# Sheet1.net
KiCad netlist of a schematic drawn in Altium Designer
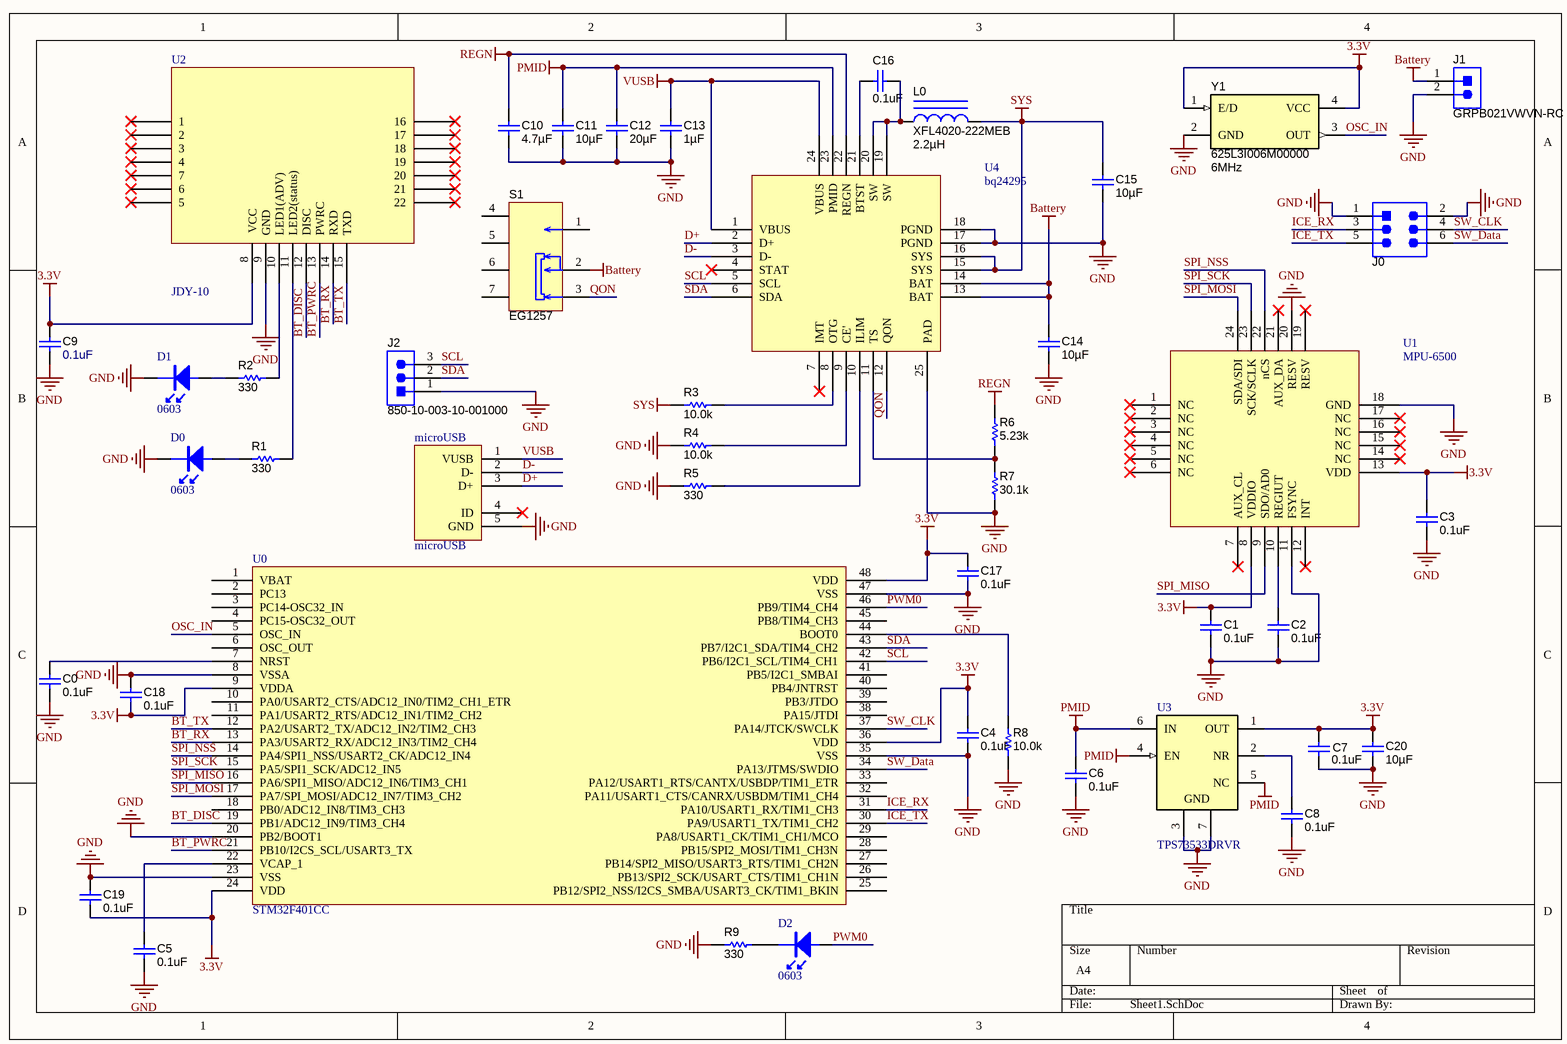
[diagram p0: Sheet1.SchDoc]

(export (version "E")
  (design (tool "Eeschema 10.0.6"))
  (components
    (comp (ref "C0")
      (value "0402YC132KAT2A")
      (footprint "0402S")
      (description "CAP, CERM, 1300 pF, 16 V, +/- 10%, X7R, 0402")
      (fields
        (field (name "VALUEDISPLAYED") "0.1uF")
        (field (name "MANUFACTURER") "AVX")
        (field (name "PUBLISHER") "Texas Instruments")
      )
      (libsource (lib "Capacitor_Ceramic") (part "0402YC132KAT2A"))
    )
    (comp (ref "C1")
      (value "0402YC132KAT2A")
      (footprint "0402S")
      (description "CAP, CERM, 1300 pF, 16 V, +/- 10%, X7R, 0402")
      (fields
        (field (name "VALUEDISPLAYED") "0.1uF")
        (field (name "MANUFACTURER") "AVX")
        (field (name "PUBLISHER") "Texas Instruments")
      )
      (libsource (lib "Capacitor_Ceramic") (part "0402YC132KAT2A"))
    )
    (comp (ref "C2")
      (value "0402YC132KAT2A")
      (footprint "0402S")
      (description "CAP, CERM, 1300 pF, 16 V, +/- 10%, X7R, 0402")
      (fields
        (field (name "VALUEDISPLAYED") "0.1uF")
        (field (name "MANUFACTURER") "AVX")
        (field (name "PUBLISHER") "Texas Instruments")
      )
      (libsource (lib "Capacitor_Ceramic") (part "0402YC132KAT2A"))
    )
    (comp (ref "C3")
      (value "0402YC132KAT2A")
      (footprint "0402S")
      (description "CAP, CERM, 1300 pF, 16 V, +/- 10%, X7R, 0402")
      (fields
        (field (name "VALUEDISPLAYED") "0.1uF")
        (field (name "MANUFACTURER") "AVX")
        (field (name "PUBLISHER") "Texas Instruments")
      )
      (libsource (lib "Capacitor_Ceramic") (part "0402YC132KAT2A"))
    )
    (comp (ref "C4")
      (value "0402YC132KAT2A")
      (footprint "0402S")
      (description "CAP, CERM, 1300 pF, 16 V, +/- 10%, X7R, 0402")
      (fields
        (field (name "VALUEDISPLAYED") "0.1uF")
        (field (name "MANUFACTURER") "AVX")
        (field (name "PUBLISHER") "Texas Instruments")
      )
      (libsource (lib "Capacitor_Ceramic") (part "0402YC132KAT2A"))
    )
    (comp (ref "C5")
      (value "0402YC132KAT2A")
      (footprint "0402S")
      (description "CAP, CERM, 1300 pF, 16 V, +/- 10%, X7R, 0402")
      (fields
        (field (name "VALUEDISPLAYED") "0.1uF")
        (field (name "MANUFACTURER") "AVX")
        (field (name "PUBLISHER") "Texas Instruments")
      )
      (libsource (lib "Capacitor_Ceramic") (part "0402YC132KAT2A"))
    )
    (comp (ref "C6")
      (value "0402YC132KAT2A")
      (footprint "0402S")
      (description "CAP, CERM, 1300 pF, 16 V, +/- 10%, X7R, 0402")
      (fields
        (field (name "VALUEDISPLAYED") "0.1uF")
        (field (name "MANUFACTURER") "AVX")
        (field (name "PUBLISHER") "Texas Instruments")
      )
      (libsource (lib "Capacitor_Ceramic") (part "0402YC132KAT2A"))
    )
    (comp (ref "C7")
      (value "0402YC132KAT2A")
      (footprint "0402S")
      (description "CAP, CERM, 1300 pF, 16 V, +/- 10%, X7R, 0402")
      (fields
        (field (name "VALUEDISPLAYED") "0.1uF")
        (field (name "MANUFACTURER") "AVX")
        (field (name "PUBLISHER") "Texas Instruments")
      )
      (libsource (lib "Capacitor_Ceramic") (part "0402YC132KAT2A"))
    )
    (comp (ref "C8")
      (value "0402YC132KAT2A")
      (footprint "0402S")
      (description "CAP, CERM, 1300 pF, 16 V, +/- 10%, X7R, 0402")
      (fields
        (field (name "VALUEDISPLAYED") "0.1uF")
        (field (name "MANUFACTURER") "AVX")
        (field (name "PUBLISHER") "Texas Instruments")
      )
      (libsource (lib "Capacitor_Ceramic") (part "0402YC132KAT2A"))
    )
    (comp (ref "C9")
      (value "0402YC132KAT2A")
      (footprint "0402S")
      (description "CAP, CERM, 1300 pF, 16 V, +/- 10%, X7R, 0402")
      (fields
        (field (name "VALUEDISPLAYED") "0.1uF")
        (field (name "MANUFACTURER") "AVX")
        (field (name "PUBLISHER") "Texas Instruments")
      )
      (libsource (lib "Capacitor_Ceramic") (part "0402YC132KAT2A"))
    )
    (comp (ref "C10")
      (value "VJ1206Y473KXEAT5Z")
      (footprint "0603L")
      (description "CAP, CERM, 0.047 µF, 500 V, +/- 10%, X7R, 1206")
      (fields
        (field (name "VALUEDISPLAYED") "4.7µF")
        (field (name "MANUFACTURER") "Vishay-Vitramon")
        (field (name "PUBLISHER") "Texas Instruments")
      )
      (libsource (lib "Capacitor_Ceramic") (part "VJ1206Y473KXEAT5Z"))
    )
    (comp (ref "C11")
      (value "VJ1206Y473KXEAT5Z")
      (footprint "0805L")
      (description "CAP, CERM, 0.047 µF, 500 V, +/- 10%, X7R, 1206")
      (fields
        (field (name "VALUEDISPLAYED") "10µF")
        (field (name "MANUFACTURER") "Vishay-Vitramon")
        (field (name "PUBLISHER") "Texas Instruments")
      )
      (libsource (lib "Capacitor_Ceramic") (part "VJ1206Y473KXEAT5Z"))
    )
    (comp (ref "C12")
      (value "VJ1206Y473KXEAT5Z")
      (footprint "0805L")
      (description "CAP, CERM, 0.047 µF, 500 V, +/- 10%, X7R, 1206")
      (fields
        (field (name "VALUEDISPLAYED") "20µF")
        (field (name "MANUFACTURER") "Vishay-Vitramon")
        (field (name "PUBLISHER") "Texas Instruments")
      )
      (libsource (lib "Capacitor_Ceramic") (part "VJ1206Y473KXEAT5Z"))
    )
    (comp (ref "C13")
      (value "0402YC132KAT2A")
      (footprint "0402S")
      (description "CAP, CERM, 1300 pF, 16 V, +/- 10%, X7R, 0402")
      (fields
        (field (name "VALUEDISPLAYED") "1µF")
        (field (name "MANUFACTURER") "AVX")
        (field (name "PUBLISHER") "Texas Instruments")
      )
      (libsource (lib "Capacitor_Ceramic") (part "0402YC132KAT2A"))
    )
    (comp (ref "C14")
      (value "VJ1206Y473KXEAT5Z")
      (footprint "0805L")
      (description "CAP, CERM, 0.047 µF, 500 V, +/- 10%, X7R, 1206")
      (fields
        (field (name "VALUEDISPLAYED") "10µF")
        (field (name "MANUFACTURER") "Vishay-Vitramon")
        (field (name "PUBLISHER") "Texas Instruments")
      )
      (libsource (lib "Capacitor_Ceramic") (part "VJ1206Y473KXEAT5Z"))
    )
    (comp (ref "C15")
      (value "VJ1206Y473KXEAT5Z")
      (footprint "0805L")
      (description "CAP, CERM, 0.047 µF, 500 V, +/- 10%, X7R, 1206")
      (fields
        (field (name "VALUEDISPLAYED") "10µF")
        (field (name "MANUFACTURER") "Vishay-Vitramon")
        (field (name "PUBLISHER") "Texas Instruments")
      )
      (libsource (lib "Capacitor_Ceramic") (part "VJ1206Y473KXEAT5Z"))
    )
    (comp (ref "C16")
      (value "0402YC132KAT2A")
      (footprint "0402S")
      (description "CAP, CERM, 1300 pF, 16 V, +/- 10%, X7R, 0402")
      (fields
        (field (name "VALUEDISPLAYED") "0.1uF")
        (field (name "MANUFACTURER") "AVX")
        (field (name "PUBLISHER") "Texas Instruments")
      )
      (libsource (lib "Capacitor_Ceramic") (part "0402YC132KAT2A"))
    )
    (comp (ref "C17")
      (value "0402YC132KAT2A")
      (footprint "0402S")
      (description "CAP, CERM, 1300 pF, 16 V, +/- 10%, X7R, 0402")
      (fields
        (field (name "VALUEDISPLAYED") "0.1uF")
        (field (name "MANUFACTURER") "AVX")
        (field (name "PUBLISHER") "Texas Instruments")
      )
      (libsource (lib "Capacitor_Ceramic") (part "0402YC132KAT2A"))
    )
    (comp (ref "C18")
      (value "0402YC132KAT2A")
      (footprint "0402S")
      (description "CAP, CERM, 1300 pF, 16 V, +/- 10%, X7R, 0402")
      (fields
        (field (name "VALUEDISPLAYED") "0.1uF")
        (field (name "MANUFACTURER") "AVX")
        (field (name "PUBLISHER") "Texas Instruments")
      )
      (libsource (lib "Capacitor_Ceramic") (part "0402YC132KAT2A"))
    )
    (comp (ref "C19")
      (value "0402YC132KAT2A")
      (footprint "0402S")
      (description "CAP, CERM, 1300 pF, 16 V, +/- 10%, X7R, 0402")
      (fields
        (field (name "VALUEDISPLAYED") "0.1uF")
        (field (name "MANUFACTURER") "AVX")
        (field (name "PUBLISHER") "Texas Instruments")
      )
      (libsource (lib "Capacitor_Ceramic") (part "0402YC132KAT2A"))
    )
    (comp (ref "C20")
      (value "VJ1206Y473KXEAT5Z")
      (footprint "0805L")
      (description "CAP, CERM, 0.047 µF, 500 V, +/- 10%, X7R, 1206")
      (fields
        (field (name "VALUEDISPLAYED") "10µF")
        (field (name "MANUFACTURER") "Vishay-Vitramon")
        (field (name "PUBLISHER") "Texas Instruments")
      )
      (libsource (lib "Capacitor_Ceramic") (part "VJ1206Y473KXEAT5Z"))
    )
    (comp (ref "D0")
      (value "0603")
      (footprint "LED_0603")
      (libsource (lib "Basic_part_ecsl") (part "LED_0603"))
    )
    (comp (ref "D1")
      (value "0603")
      (footprint "LED_0603")
      (libsource (lib "Basic_part_ecsl") (part "LED_0603"))
    )
    (comp (ref "D2")
      (value "0603")
      (footprint "LED_0603")
      (libsource (lib "Basic_part_ecsl") (part "LED_0603"))
    )
    (comp (ref "J0")
      (value "GRPB032VWVN-RC")
      (footprint "Sullins_GRPB032VWVN-RC")
      (description "Header, 50mil, 3x2, Gold, TH")
      (fields
        (field (name "MANUFACTURER") "Sullins Connector Solutions")
        (field (name "SYMBOLCREATOR") "a0412235")
        (field (name "PUBLISHER") "Texas Instruments")
      )
      (libsource (lib "Connectors") (part "GRPB032VWVN-RC"))
    )
    (comp (ref "J1")
      (value "GRPB021VWVN-RC")
      (footprint "Sullins_GRPB021VWVN-RC")
      (description "Header, 50mil, 2x1, Gold, TH")
      (fields
        (field (name "MANUFACTURER") "Sullins Connector Solutions")
        (field (name "SYMBOLCREATOR") "a0412235")
        (field (name "PUBLISHER") "Texas Instruments")
      )
      (libsource (lib "Connectors") (part "GRPB021VWVN-RC"))
    )
    (comp (ref "J2")
      (value "850-10-003-10-001000")
      (footprint "Mill-Max_850-10-003-10-001000")
      (description "Header, 50mil, 3x1, Gold, TH")
      (fields
        (field (name "MANUFACTURER") "Mill-Max")
        (field (name "SYMBOLCREATOR") "a0799628")
        (field (name "PUBLISHER") "Texas Instruments")
      )
      (libsource (lib "Connectors") (part "850-10-003-10-001000"))
    )
    (comp (ref "L0")
      (value "XFL4020-222MEB")
      (footprint "XFL4020")
      (description "Inductor, Shielded, Composite, 2.2uH, 3.7A, 0.02 ohm, SMD")
      (fields
        (field (name "VALUEDISPLAYED") "2.2µH")
        (field (name "MANUFACTURER") "Coilcraft")
        (field (name "PUBLISHER") "Texas Instruments")
      )
      (libsource (lib "Inductor") (part "XFL4020-222MEB"))
    )
    (comp (ref "microUSB")
      (value "microUSB")
      (footprint "Micro_USB")
      (libsource (lib "Basic_part_ecsl") (part "microUSB"))
    )
    (comp (ref "R1")
      (value "PCF0402-12-10KBT1")
      (footprint "0402S")
      (description "RES, 10.0 k, 0.1%, 0.063 W, 0402")
      (fields
        (field (name "VALUEDISPLAYED") "330")
        (field (name "MANUFACTURER") "TT Electronics/IRC")
        (field (name "PUBLISHER") "Texas Instruments")
      )
      (libsource (lib "Resistor_0402") (part "PCF0402-12-10KBT1"))
    )
    (comp (ref "R2")
      (value "PCF0402-12-10KBT1")
      (footprint "0402S")
      (description "RES, 10.0 k, 0.1%, 0.063 W, 0402")
      (fields
        (field (name "VALUEDISPLAYED") "330")
        (field (name "MANUFACTURER") "TT Electronics/IRC")
        (field (name "PUBLISHER") "Texas Instruments")
      )
      (libsource (lib "Resistor_0402") (part "PCF0402-12-10KBT1"))
    )
    (comp (ref "R3")
      (value "PCF0402-12-10KBT1")
      (footprint "0402S")
      (description "RES, 10.0 k, 0.1%, 0.063 W, 0402")
      (fields
        (field (name "VALUEDISPLAYED") "10.0k")
        (field (name "MANUFACTURER") "TT Electronics/IRC")
        (field (name "PUBLISHER") "Texas Instruments")
      )
      (libsource (lib "Resistor_0402") (part "PCF0402-12-10KBT1"))
    )
    (comp (ref "R4")
      (value "PCF0402-12-10KBT1")
      (footprint "0402S")
      (description "RES, 10.0 k, 0.1%, 0.063 W, 0402")
      (fields
        (field (name "VALUEDISPLAYED") "10.0k")
        (field (name "MANUFACTURER") "TT Electronics/IRC")
        (field (name "PUBLISHER") "Texas Instruments")
      )
      (libsource (lib "Resistor_0402") (part "PCF0402-12-10KBT1"))
    )
    (comp (ref "R5")
      (value "PCF0402-12-10KBT1")
      (footprint "0402S")
      (description "RES, 10.0 k, 0.1%, 0.063 W, 0402")
      (fields
        (field (name "VALUEDISPLAYED") "330")
        (field (name "MANUFACTURER") "TT Electronics/IRC")
        (field (name "PUBLISHER") "Texas Instruments")
      )
      (libsource (lib "Resistor_0402") (part "PCF0402-12-10KBT1"))
    )
    (comp (ref "R6")
      (value "PCF0402-12-10KBT1")
      (footprint "0402S")
      (description "RES, 10.0 k, 0.1%, 0.063 W, 0402")
      (fields
        (field (name "VALUEDISPLAYED") "5.23k")
        (field (name "MANUFACTURER") "TT Electronics/IRC")
        (field (name "PUBLISHER") "Texas Instruments")
      )
      (libsource (lib "Resistor_0402") (part "PCF0402-12-10KBT1"))
    )
    (comp (ref "R7")
      (value "PCF0402-12-10KBT1")
      (footprint "0402S")
      (description "RES, 10.0 k, 0.1%, 0.063 W, 0402")
      (fields
        (field (name "VALUEDISPLAYED") "30.1k")
        (field (name "MANUFACTURER") "TT Electronics/IRC")
        (field (name "PUBLISHER") "Texas Instruments")
      )
      (libsource (lib "Resistor_0402") (part "PCF0402-12-10KBT1"))
    )
    (comp (ref "R8")
      (value "PCF0402-12-10KBT1")
      (footprint "0402S")
      (description "RES, 10.0 k, 0.1%, 0.063 W, 0402")
      (fields
        (field (name "VALUEDISPLAYED") "10.0k")
        (field (name "MANUFACTURER") "TT Electronics/IRC")
        (field (name "PUBLISHER") "Texas Instruments")
      )
      (libsource (lib "Resistor_0402") (part "PCF0402-12-10KBT1"))
    )
    (comp (ref "R9")
      (value "PCF0402-12-10KBT1")
      (footprint "0402S")
      (description "RES, 10.0 k, 0.1%, 0.063 W, 0402")
      (fields
        (field (name "VALUEDISPLAYED") "330")
        (field (name "MANUFACTURER") "TT Electronics/IRC")
        (field (name "PUBLISHER") "Texas Instruments")
      )
      (libsource (lib "Resistor_0402") (part "PCF0402-12-10KBT1"))
    )
    (comp (ref "S1")
      (value "EG1257")
      (footprint "SW_EG1257")
      (description "Switch, Slide, SPDT, 0.3A, SMT")
      (fields
        (field (name "MANUFACTURER") "E-Switch")
        (field (name "SYMBOLCREATOR") "a0411947")
        (field (name "PUBLISHER") "Texas Instruments")
      )
      (libsource (lib "Switches") (part "EG1257"))
    )
    (comp (ref "U0")
      (value "STM32F401CC")
      (footprint "RSL0048B_NV")
      (libsource (lib "main") (part "STM32F401CC"))
    )
    (comp (ref "U1")
      (value "MPU-6500")
      (footprint "QFN24 (3x3x0.9)")
      (libsource (lib "Basic_part_ecsl") (part "MPU-6500"))
    )
    (comp (ref "U2")
      (value "JDY-10")
      (footprint "PCBComponent_1")
      (libsource (lib "JDY-10") (part "Component_1"))
    )
    (comp (ref "U3")
      (value "TPS73533DRVR")
      (footprint "DRV0006A")
      (fields
        (field (name "MANUFACTURER") "Texas Instruments")
        (field (name "ALTERNATE PARTNUMBER") "Equivalent")
      )
      (libsource (lib "TI Power Management Linear Regulator Single Channel LDO (400-7500mA)") (part "TPS73533DRVR"))
    )
    (comp (ref "U4")
      (value "bq24295")
      (footprint "RGE0024H_NV")
      (libsource (lib "Basic_part_ecsl") (part "bq24295"))
    )
    (comp (ref "Y1")
      (value "625L3I006M00000")
      (footprint "OSC_CTS_625")
      (description "Oscillator, 6MHz, 3.3V, SMD")
      (fields
        (field (name "FREQUENCY") "6MHz")
        (field (name "MANUFACTURER") "CTS Electrocomponents")
        (field (name "SYMBOLCREATOR") "a0411947")
        (field (name "PUBLISHER") "Texas Instruments")
      )
      (libsource (lib "Oscillators") (part "625L3I006M00000"))
    )
  )
  (nets
    (net (code "1") (name "/BT_DISC") (class "Default")
      (node (ref "U0") (pin "19") (pinfunction "PB1/ADC12_IN9/TIM3_CH4_19") (pintype "passive"))
      (node (ref "U2") (pin "12") (pinfunction "DISC_12") (pintype "passive"))
    )
    (net (code "2") (name "/BT_PWRC") (class "Default")
      (node (ref "U0") (pin "21") (pinfunction "PB10/I2CS_SCL/USART3_TX_21") (pintype "passive"))
      (node (ref "U2") (pin "13") (pinfunction "PWRC_13") (pintype "passive"))
    )
    (net (code "3") (name "/BT_RX") (class "Default")
      (node (ref "U0") (pin "13") (pinfunction "PA3/USART2_RX/ADC12_IN3/TIM2_CH4_13") (pintype "passive"))
      (node (ref "U2") (pin "14") (pinfunction "RXD_14") (pintype "passive"))
    )
    (net (code "4") (name "/BT_TX") (class "Default")
      (node (ref "U0") (pin "12") (pinfunction "PA2/USART2_TX/ADC12_IN2/TIM2_CH3_12") (pintype "passive"))
      (node (ref "U2") (pin "15") (pinfunction "TXD_15") (pintype "passive"))
    )
    (net (code "5") (name "/D+") (class "Default")
      (node (ref "U4") (pin "2") (pinfunction "D+_2") (pintype "passive"))
      (node (ref "microUSB") (pin "3") (pinfunction "D+_3") (pintype "passive"))
    )
    (net (code "6") (name "/D-") (class "Default")
      (node (ref "U4") (pin "3") (pinfunction "D-_3") (pintype "passive"))
      (node (ref "microUSB") (pin "2") (pinfunction "D-_2") (pintype "passive"))
    )
    (net (code "7") (name "/ICE_RX") (class "Default")
      (node (ref "J0") (pin "3") (pinfunction "3_3") (pintype "passive"))
      (node (ref "U0") (pin "31") (pinfunction "PA10/USART1_RX/TIM1_CH3_31") (pintype "passive"))
    )
    (net (code "8") (name "/ICE_TX") (class "Default")
      (node (ref "J0") (pin "5") (pinfunction "5_5") (pintype "passive"))
      (node (ref "U0") (pin "30") (pinfunction "PA9/USART1_TX/TIM1_CH2_30") (pintype "passive"))
    )
    (net (code "9") (name "/OSC_IN") (class "Default")
      (node (ref "U0") (pin "5") (pinfunction "OSC_IN_5") (pintype "passive"))
      (node (ref "Y1") (pin "3") (pinfunction "OUT_3") (pintype "output"))
    )
    (net (code "10") (name "/PWM0") (class "Default")
      (node (ref "D2") (pin "1") (pinfunction "1_1") (pintype "passive"))
      (node (ref "U0") (pin "46") (pinfunction "PB9/TIM4_CH4_46") (pintype "passive"))
    )
    (net (code "11") (name "/QON") (class "Default")
      (node (ref "S1") (pin "3") (pinfunction "3_3") (pintype "passive"))
      (node (ref "U4") (pin "12") (pinfunction "QON_12") (pintype "passive"))
    )
    (net (code "12") (name "/SCL") (class "Default")
      (node (ref "J2") (pin "3") (pinfunction "3_3") (pintype "passive"))
      (node (ref "U0") (pin "42") (pinfunction "PB6/I2C1_SCL/TIM4_CH1_42") (pintype "passive"))
      (node (ref "U4") (pin "5") (pinfunction "SCL_5") (pintype "passive"))
    )
    (net (code "13") (name "/SDA") (class "Default")
      (node (ref "J2") (pin "2") (pinfunction "2_2") (pintype "passive"))
      (node (ref "U0") (pin "43") (pinfunction "PB7/I2C1_SDA/TIM4_CH2_43") (pintype "passive"))
      (node (ref "U4") (pin "6") (pinfunction "SDA_6") (pintype "passive"))
    )
    (net (code "14") (name "/SPI_MISO") (class "Default")
      (node (ref "U0") (pin "16") (pinfunction "PA6/SPI1_MISO/ADC12_IN6/TIM3_CH1_16") (pintype "passive"))
      (node (ref "U1") (pin "9") (pinfunction "SDO/AD0_9") (pintype "passive"))
    )
    (net (code "15") (name "/SPI_MOSI") (class "Default")
      (node (ref "U0") (pin "17") (pinfunction "PA7/SPI_MOSI/ADC12_IN7/TIM3_CH2_17") (pintype "passive"))
      (node (ref "U1") (pin "24") (pinfunction "SDA/SDI_24") (pintype "passive"))
    )
    (net (code "16") (name "/SPI_NSS") (class "Default")
      (node (ref "U0") (pin "14") (pinfunction "PA4/SPI1_NSS/USART2_CK/ADC12_IN4_14") (pintype "passive"))
      (node (ref "U1") (pin "22") (pinfunction "nCS_22") (pintype "passive"))
    )
    (net (code "17") (name "/SPI_SCK") (class "Default")
      (node (ref "U0") (pin "15") (pinfunction "PA5/SPI1_SCK/ADC12_IN5_15") (pintype "passive"))
      (node (ref "U1") (pin "23") (pinfunction "SCK/SCLK_23") (pintype "passive"))
    )
    (net (code "18") (name "/SW_CLK") (class "Default")
      (node (ref "J0") (pin "4") (pinfunction "4_4") (pintype "passive"))
      (node (ref "U0") (pin "37") (pinfunction "PA14/JTCK/SWCLK_37") (pintype "passive"))
    )
    (net (code "19") (name "/SW_Data") (class "Default")
      (node (ref "J0") (pin "6") (pinfunction "6_6") (pintype "passive"))
      (node (ref "U0") (pin "34") (pinfunction "PA13/JTMS/SWDIO_34") (pintype "passive"))
    )
    (net (code "20") (name "3.3V") (class "Default")
      (node (ref "C1") (pin "1") (pinfunction "1_1") (pintype "passive"))
      (node (ref "C17") (pin "1") (pinfunction "1_1") (pintype "passive"))
      (node (ref "C18") (pin "2") (pinfunction "2_2") (pintype "passive"))
      (node (ref "C19") (pin "2") (pinfunction "2_2") (pintype "passive"))
      (node (ref "C20") (pin "1") (pinfunction "1_1") (pintype "passive"))
      (node (ref "C3") (pin "1") (pinfunction "1_1") (pintype "passive"))
      (node (ref "C4") (pin "1") (pinfunction "1_1") (pintype "passive"))
      (node (ref "C7") (pin "1") (pinfunction "1_1") (pintype "passive"))
      (node (ref "C9") (pin "1") (pinfunction "1_1") (pintype "passive"))
      (node (ref "U0") (pin "24") (pinfunction "VDD_24") (pintype "passive"))
      (node (ref "U0") (pin "36") (pinfunction "VDD_36") (pintype "passive"))
      (node (ref "U0") (pin "48") (pinfunction "VDD_48") (pintype "passive"))
      (node (ref "U0") (pin "9") (pinfunction "VDDA_9") (pintype "passive"))
      (node (ref "U1") (pin "13") (pinfunction "VDD_13") (pintype "passive"))
      (node (ref "U1") (pin "8") (pinfunction "VDDIO_8") (pintype "passive"))
      (node (ref "U2") (pin "8") (pinfunction "VCC_8") (pintype "power_in"))
      (node (ref "U3") (pin "1") (pinfunction "OUT_1") (pintype "power_in"))
      (node (ref "Y1") (pin "1") (pinfunction "E/D_1") (pintype "input"))
      (node (ref "Y1") (pin "4") (pinfunction "VCC_4") (pintype "power_in"))
    )
    (net (code "21") (name "Battery") (class "Default")
      (node (ref "C14") (pin "1") (pinfunction "1_1") (pintype "passive"))
      (node (ref "J1") (pin "1") (pinfunction "1_1") (pintype "passive"))
      (node (ref "S1") (pin "2") (pinfunction "2_2") (pintype "passive"))
      (node (ref "U4") (pin "13") (pinfunction "BAT_13") (pintype "passive"))
      (node (ref "U4") (pin "14") (pinfunction "BAT_14") (pintype "passive"))
    )
    (net (code "22") (name "GND") (class "Default")
      (node (ref "C0") (pin "2") (pinfunction "2_2") (pintype "passive"))
      (node (ref "C1") (pin "2") (pinfunction "2_2") (pintype "passive"))
      (node (ref "C10") (pin "2") (pinfunction "2_2") (pintype "passive"))
      (node (ref "C11") (pin "2") (pinfunction "2_2") (pintype "passive"))
      (node (ref "C12") (pin "2") (pinfunction "2_2") (pintype "passive"))
      (node (ref "C13") (pin "2") (pinfunction "2_2") (pintype "passive"))
      (node (ref "C14") (pin "2") (pinfunction "2_2") (pintype "passive"))
      (node (ref "C15") (pin "2") (pinfunction "2_2") (pintype "passive"))
      (node (ref "C17") (pin "2") (pinfunction "2_2") (pintype "passive"))
      (node (ref "C18") (pin "1") (pinfunction "1_1") (pintype "passive"))
      (node (ref "C19") (pin "1") (pinfunction "1_1") (pintype "passive"))
      (node (ref "C2") (pin "2") (pinfunction "2_2") (pintype "passive"))
      (node (ref "C20") (pin "2") (pinfunction "2_2") (pintype "passive"))
      (node (ref "C3") (pin "2") (pinfunction "2_2") (pintype "passive"))
      (node (ref "C4") (pin "2") (pinfunction "2_2") (pintype "passive"))
      (node (ref "C5") (pin "2") (pinfunction "2_2") (pintype "passive"))
      (node (ref "C6") (pin "2") (pinfunction "2_2") (pintype "passive"))
      (node (ref "C7") (pin "2") (pinfunction "2_2") (pintype "passive"))
      (node (ref "C8") (pin "2") (pinfunction "2_2") (pintype "passive"))
      (node (ref "C9") (pin "2") (pinfunction "2_2") (pintype "passive"))
      (node (ref "D0") (pin "2") (pinfunction "2_2") (pintype "passive"))
      (node (ref "D1") (pin "2") (pinfunction "2_2") (pintype "passive"))
      (node (ref "J0") (pin "1") (pinfunction "1_1") (pintype "passive"))
      (node (ref "J0") (pin "2") (pinfunction "2_2") (pintype "passive"))
      (node (ref "J1") (pin "2") (pinfunction "2_2") (pintype "passive"))
      (node (ref "J2") (pin "1") (pinfunction "1_1") (pintype "passive"))
      (node (ref "R4") (pin "1") (pinfunction "1_1") (pintype "passive"))
      (node (ref "R5") (pin "1") (pinfunction "1_1") (pintype "passive"))
      (node (ref "R7") (pin "1") (pinfunction "1_1") (pintype "passive"))
      (node (ref "R8") (pin "1") (pinfunction "1_1") (pintype "passive"))
      (node (ref "R9") (pin "1") (pinfunction "1_1") (pintype "passive"))
      (node (ref "U0") (pin "20") (pinfunction "PB2/BOOT1_20") (pintype "passive"))
      (node (ref "U0") (pin "23") (pinfunction "VSS_23") (pintype "passive"))
      (node (ref "U0") (pin "35") (pinfunction "VSS_35") (pintype "passive"))
      (node (ref "U0") (pin "47") (pinfunction "VSS_47") (pintype "passive"))
      (node (ref "U0") (pin "8") (pinfunction "VSSA_8") (pintype "passive"))
      (node (ref "U1") (pin "11") (pinfunction "FSYNC_11") (pintype "passive"))
      (node (ref "U1") (pin "18") (pinfunction "GND_18") (pintype "passive"))
      (node (ref "U1") (pin "20") (pinfunction "RESV_20") (pintype "passive"))
      (node (ref "U2") (pin "9") (pinfunction "GND_9") (pintype "passive"))
      (node (ref "U3") (pin "3") (pinfunction "GND_3") (pintype "power_in"))
      (node (ref "U3") (pin "7") (pinfunction "GND_7") (pintype "power_in"))
      (node (ref "U4") (pin "17") (pinfunction "PGND_17") (pintype "passive"))
      (node (ref "U4") (pin "18") (pinfunction "PGND_18") (pintype "passive"))
      (node (ref "U4") (pin "25") (pinfunction "PAD_25") (pintype "passive"))
      (node (ref "Y1") (pin "2") (pinfunction "GND_2") (pintype "power_in"))
      (node (ref "microUSB") (pin "5") (pinfunction "GND_5") (pintype "passive"))
    )
    (net (code "23") (name "Net-(C16-Pad1)") (class "Default")
      (node (ref "C16") (pin "1") (pinfunction "1_1") (pintype "passive"))
      (node (ref "L0") (pin "1") (pinfunction "1_1") (pintype "passive"))
      (node (ref "U4") (pin "19") (pinfunction "SW_19") (pintype "passive"))
      (node (ref "U4") (pin "20") (pinfunction "SW_20") (pintype "passive"))
    )
    (net (code "24") (name "Net-(D0-Pad1)") (class "Default")
      (node (ref "D0") (pin "1") (pinfunction "1_1") (pintype "passive"))
      (node (ref "R1") (pin "1") (pinfunction "1_1") (pintype "passive"))
    )
    (net (code "25") (name "Net-(D1-Pad1)") (class "Default")
      (node (ref "D1") (pin "1") (pinfunction "1_1") (pintype "passive"))
      (node (ref "R2") (pin "1") (pinfunction "1_1") (pintype "passive"))
    )
    (net (code "26") (name "Net-(D2-Pad2)") (class "Default")
      (node (ref "D2") (pin "2") (pinfunction "2_2") (pintype "passive"))
      (node (ref "R9") (pin "2") (pinfunction "2_2") (pintype "passive"))
    )
    (net (code "27") (name "Net-(U0-BOOT0)") (class "Default")
      (node (ref "R8") (pin "2") (pinfunction "2_2") (pintype "passive"))
      (node (ref "U0") (pin "44") (pinfunction "BOOT0_44") (pintype "passive"))
    )
    (net (code "28") (name "Net-(U0-NRST)") (class "Default")
      (node (ref "C0") (pin "1") (pinfunction "1_1") (pintype "passive"))
      (node (ref "U0") (pin "7") (pinfunction "NRST_7") (pintype "passive"))
    )
    (net (code "29") (name "Net-(U0-VCAP_1)") (class "Default")
      (node (ref "C5") (pin "1") (pinfunction "1_1") (pintype "passive"))
      (node (ref "U0") (pin "22") (pinfunction "VCAP_1_22") (pintype "passive"))
    )
    (net (code "30") (name "Net-(U1-REGIUT)") (class "Default")
      (node (ref "C2") (pin "1") (pinfunction "1_1") (pintype "passive"))
      (node (ref "U1") (pin "10") (pinfunction "REGIUT_10") (pintype "passive"))
    )
    (net (code "31") (name "Net-(U2-LED1(ADV))") (class "Default")
      (node (ref "R2") (pin "2") (pinfunction "2_2") (pintype "passive"))
      (node (ref "U2") (pin "10") (pinfunction "LED1(ADV)_10") (pintype "passive"))
    )
    (net (code "32") (name "Net-(U2-LED2(status))") (class "Default")
      (node (ref "R1") (pin "2") (pinfunction "2_2") (pintype "passive"))
      (node (ref "U2") (pin "11") (pinfunction "LED2(status)_11") (pintype "passive"))
    )
    (net (code "33") (name "Net-(U3-NR)") (class "Default")
      (node (ref "C8") (pin "1") (pinfunction "1_1") (pintype "passive"))
      (node (ref "U3") (pin "2") (pinfunction "NR_2") (pintype "passive"))
    )
    (net (code "34") (name "Net-(U4-BTST)") (class "Default")
      (node (ref "C16") (pin "2") (pinfunction "2_2") (pintype "passive"))
      (node (ref "U4") (pin "21") (pinfunction "BTST_21") (pintype "passive"))
    )
    (net (code "35") (name "Net-(U4-CE')") (class "Default")
      (node (ref "R4") (pin "2") (pinfunction "2_2") (pintype "passive"))
      (node (ref "U4") (pin "9") (pinfunction "CE'_9") (pintype "passive"))
    )
    (net (code "36") (name "Net-(U4-ILIM)") (class "Default")
      (node (ref "R5") (pin "2") (pinfunction "2_2") (pintype "passive"))
      (node (ref "U4") (pin "10") (pinfunction "ILIM_10") (pintype "passive"))
    )
    (net (code "37") (name "Net-(U4-OTG)") (class "Default")
      (node (ref "R3") (pin "2") (pinfunction "2_2") (pintype "passive"))
      (node (ref "U4") (pin "8") (pinfunction "OTG_8") (pintype "passive"))
    )
    (net (code "38") (name "Net-(U4-TS)") (class "Default")
      (node (ref "R6") (pin "1") (pinfunction "1_1") (pintype "passive"))
      (node (ref "R7") (pin "2") (pinfunction "2_2") (pintype "passive"))
      (node (ref "U4") (pin "11") (pinfunction "TS_11") (pintype "passive"))
    )
    (net (code "39") (name "PMID") (class "Default")
      (node (ref "C11") (pin "1") (pinfunction "1_1") (pintype "passive"))
      (node (ref "C12") (pin "1") (pinfunction "1_1") (pintype "passive"))
      (node (ref "C6") (pin "1") (pinfunction "1_1") (pintype "passive"))
      (node (ref "U3") (pin "4") (pinfunction "EN_4") (pintype "input"))
      (node (ref "U3") (pin "5") (pinfunction "NC_5") (pintype "passive"))
      (node (ref "U3") (pin "6") (pinfunction "IN_6") (pintype "power_in"))
      (node (ref "U4") (pin "23") (pinfunction "PMID_23") (pintype "passive"))
    )
    (net (code "40") (name "REGN") (class "Default")
      (node (ref "C10") (pin "1") (pinfunction "1_1") (pintype "passive"))
      (node (ref "R6") (pin "2") (pinfunction "2_2") (pintype "passive"))
      (node (ref "U4") (pin "22") (pinfunction "REGN_22") (pintype "passive"))
    )
    (net (code "41") (name "SYS") (class "Default")
      (node (ref "C15") (pin "1") (pinfunction "1_1") (pintype "passive"))
      (node (ref "L0") (pin "2") (pinfunction "2_2") (pintype "passive"))
      (node (ref "R3") (pin "1") (pinfunction "1_1") (pintype "passive"))
      (node (ref "U4") (pin "15") (pinfunction "SYS_15") (pintype "passive"))
      (node (ref "U4") (pin "16") (pinfunction "SYS_16") (pintype "passive"))
    )
    (net (code "42") (name "VUSB") (class "Default")
      (node (ref "C13") (pin "1") (pinfunction "1_1") (pintype "passive"))
      (node (ref "U4") (pin "1") (pinfunction "VBUS_1") (pintype "passive"))
      (node (ref "U4") (pin "24") (pinfunction "VBUS_24") (pintype "passive"))
      (node (ref "microUSB") (pin "1") (pinfunction "VUSB_1") (pintype "passive"))
    )
    (net (code "43") (name "unconnected-(S1-Pad1)") (class "Default")
      (node (ref "S1") (pin "1") (pinfunction "1_1") (pintype "passive"))
    )
    (net (code "44") (name "unconnected-(S1-Pad4)") (class "Default")
      (node (ref "S1") (pin "4") (pinfunction "4_4") (pintype "passive"))
    )
    (net (code "45") (name "unconnected-(S1-Pad5)") (class "Default")
      (node (ref "S1") (pin "5") (pinfunction "5_5") (pintype "passive"))
    )
    (net (code "46") (name "unconnected-(S1-Pad6)") (class "Default")
      (node (ref "S1") (pin "6") (pinfunction "6_6") (pintype "passive"))
    )
    (net (code "47") (name "unconnected-(S1-Pad7)") (class "Default")
      (node (ref "S1") (pin "7") (pinfunction "7_7") (pintype "passive"))
    )
    (net (code "48") (name "unconnected-(U0-OSC_OUT-Pad6)") (class "Default")
      (node (ref "U0") (pin "6") (pinfunction "OSC_OUT_6") (pintype "passive"))
    )
    (net (code "49") (name "unconnected-(U0-PA0{slash}USART2_CTS{slash}ADC12_IN0{slash}TIM2_CH1_ETR-Pad10)") (class "Default")
      (node (ref "U0") (pin "10") (pinfunction "PA0/USART2_CTS/ADC12_IN0/TIM2_CH1_ETR_10") (pintype "passive"))
    )
    (net (code "50") (name "unconnected-(U0-PA1{slash}USART2_RTS{slash}ADC12_IN1{slash}TIM2_CH2-Pad11)") (class "Default")
      (node (ref "U0") (pin "11") (pinfunction "PA1/USART2_RTS/ADC12_IN1/TIM2_CH2_11") (pintype "passive"))
    )
    (net (code "51") (name "unconnected-(U0-PA8{slash}USART1_CK{slash}TIM1_CH1{slash}MCO-Pad29)") (class "Default")
      (node (ref "U0") (pin "29") (pinfunction "PA8/USART1_CK/TIM1_CH1/MCO_29") (pintype "passive"))
    )
    (net (code "52") (name "unconnected-(U0-PA11{slash}USART1_CTS{slash}CANRX{slash}USBDM{slash}TIM1_CH4-Pad32)") (class "Default")
      (node (ref "U0") (pin "32") (pinfunction "PA11/USART1_CTS/CANRX/USBDM/TIM1_CH4_32") (pintype "passive"))
    )
    (net (code "53") (name "unconnected-(U0-PA12{slash}USART1_RTS{slash}CANTX{slash}USBDP{slash}TIM1_ETR-Pad33)") (class "Default")
      (node (ref "U0") (pin "33") (pinfunction "PA12/USART1_RTS/CANTX/USBDP/TIM1_ETR_33") (pintype "passive"))
    )
    (net (code "54") (name "unconnected-(U0-PA15{slash}JTDI-Pad38)") (class "Default")
      (node (ref "U0") (pin "38") (pinfunction "PA15/JTDI_38") (pintype "passive"))
    )
    (net (code "55") (name "unconnected-(U0-PB0{slash}ADC12_IN8{slash}TIM3_CH3-Pad18)") (class "Default")
      (node (ref "U0") (pin "18") (pinfunction "PB0/ADC12_IN8/TIM3_CH3_18") (pintype "passive"))
    )
    (net (code "56") (name "unconnected-(U0-PB3{slash}JTDO-Pad39)") (class "Default")
      (node (ref "U0") (pin "39") (pinfunction "PB3/JTDO_39") (pintype "passive"))
    )
    (net (code "57") (name "unconnected-(U0-PB4{slash}JNTRST-Pad40)") (class "Default")
      (node (ref "U0") (pin "40") (pinfunction "PB4/JNTRST_40") (pintype "passive"))
    )
    (net (code "58") (name "unconnected-(U0-PB5{slash}I2C1_SMBAI-Pad41)") (class "Default")
      (node (ref "U0") (pin "41") (pinfunction "PB5/I2C1_SMBAI_41") (pintype "passive"))
    )
    (net (code "59") (name "unconnected-(U0-PB8{slash}TIM4_CH3-Pad45)") (class "Default")
      (node (ref "U0") (pin "45") (pinfunction "PB8/TIM4_CH3_45") (pintype "passive"))
    )
    (net (code "60") (name "unconnected-(U0-PB12{slash}SPI2_NSS{slash}I2CS_SMBA{slash}USART3_CK{slash}TIM1_BKIN-Pad25)") (class "Default")
      (node (ref "U0") (pin "25") (pinfunction "PB12/SPI2_NSS/I2CS_SMBA/USART3_CK/TIM1_BKIN_25") (pintype "passive"))
    )
    (net (code "61") (name "unconnected-(U0-PB13{slash}SPI2_SCK{slash}USART_CTS{slash}TIM1_CH1N-Pad26)") (class "Default")
      (node (ref "U0") (pin "26") (pinfunction "PB13/SPI2_SCK/USART_CTS/TIM1_CH1N_26") (pintype "passive"))
    )
    (net (code "62") (name "unconnected-(U0-PB14{slash}SPI2_MISO{slash}USART3_RTS{slash}TIM1_CH2N-Pad27)") (class "Default")
      (node (ref "U0") (pin "27") (pinfunction "PB14/SPI2_MISO/USART3_RTS/TIM1_CH2N_27") (pintype "passive"))
    )
    (net (code "63") (name "unconnected-(U0-PB15{slash}SPI2_MOSI{slash}TIM1_CH3N-Pad28)") (class "Default")
      (node (ref "U0") (pin "28") (pinfunction "PB15/SPI2_MOSI/TIM1_CH3N_28") (pintype "passive"))
    )
    (net (code "64") (name "unconnected-(U0-PC13-Pad2)") (class "Default")
      (node (ref "U0") (pin "2") (pinfunction "PC13_2") (pintype "passive"))
    )
    (net (code "65") (name "unconnected-(U0-PC14-OSC32_IN-Pad3)") (class "Default")
      (node (ref "U0") (pin "3") (pinfunction "PC14-OSC32_IN_3") (pintype "passive"))
    )
    (net (code "66") (name "unconnected-(U0-PC15-OSC32_OUT-Pad4)") (class "Default")
      (node (ref "U0") (pin "4") (pinfunction "PC15-OSC32_OUT_4") (pintype "passive"))
    )
    (net (code "67") (name "unconnected-(U0-VBAT-Pad1)") (class "Default")
      (node (ref "U0") (pin "1") (pinfunction "VBAT_1") (pintype "passive"))
    )
    (net (code "68") (name "unconnected-(U1-AUX_CL-Pad7)") (class "Default")
      (node (ref "U1") (pin "7") (pinfunction "AUX_CL_7") (pintype "passive+no_connect"))
    )
    (net (code "69") (name "unconnected-(U1-AUX_DA-Pad21)") (class "Default")
      (node (ref "U1") (pin "21") (pinfunction "AUX_DA_21") (pintype "passive+no_connect"))
    )
    (net (code "70") (name "unconnected-(U1-INT-Pad12)") (class "Default")
      (node (ref "U1") (pin "12") (pinfunction "INT_12") (pintype "passive+no_connect"))
    )
    (net (code "71") (name "unconnected-(U1-NC-Pad1)") (class "Default")
      (node (ref "U1") (pin "1") (pinfunction "NC_1") (pintype "passive+no_connect"))
    )
    (net (code "72") (name "unconnected-(U1-NC-Pad2)") (class "Default")
      (node (ref "U1") (pin "2") (pinfunction "NC_2") (pintype "passive+no_connect"))
    )
    (net (code "73") (name "unconnected-(U1-NC-Pad3)") (class "Default")
      (node (ref "U1") (pin "3") (pinfunction "NC_3") (pintype "passive+no_connect"))
    )
    (net (code "74") (name "unconnected-(U1-NC-Pad4)") (class "Default")
      (node (ref "U1") (pin "4") (pinfunction "NC_4") (pintype "passive+no_connect"))
    )
    (net (code "75") (name "unconnected-(U1-NC-Pad5)") (class "Default")
      (node (ref "U1") (pin "5") (pinfunction "NC_5") (pintype "passive+no_connect"))
    )
    (net (code "76") (name "unconnected-(U1-NC-Pad6)") (class "Default")
      (node (ref "U1") (pin "6") (pinfunction "NC_6") (pintype "passive+no_connect"))
    )
    (net (code "77") (name "unconnected-(U1-NC-Pad14)") (class "Default")
      (node (ref "U1") (pin "14") (pinfunction "NC_14") (pintype "passive+no_connect"))
    )
    (net (code "78") (name "unconnected-(U1-NC-Pad15)") (class "Default")
      (node (ref "U1") (pin "15") (pinfunction "NC_15") (pintype "passive+no_connect"))
    )
    (net (code "79") (name "unconnected-(U1-NC-Pad16)") (class "Default")
      (node (ref "U1") (pin "16") (pinfunction "NC_16") (pintype "passive+no_connect"))
    )
    (net (code "80") (name "unconnected-(U1-NC-Pad17)") (class "Default")
      (node (ref "U1") (pin "17") (pinfunction "NC_17") (pintype "passive+no_connect"))
    )
    (net (code "81") (name "unconnected-(U1-RESV-Pad19)") (class "Default")
      (node (ref "U1") (pin "19") (pinfunction "RESV_19") (pintype "passive+no_connect"))
    )
    (net (code "82") (name "unconnected-(U2-Pad1)") (class "Default")
      (node (ref "U2") (pin "1") (pinfunction "1_1") (pintype "passive+no_connect"))
    )
    (net (code "83") (name "unconnected-(U2-Pad2)") (class "Default")
      (node (ref "U2") (pin "2") (pinfunction "2_2") (pintype "passive+no_connect"))
    )
    (net (code "84") (name "unconnected-(U2-Pad3)") (class "Default")
      (node (ref "U2") (pin "3") (pinfunction "3_3") (pintype "passive+no_connect"))
    )
    (net (code "85") (name "unconnected-(U2-Pad4)") (class "Default")
      (node (ref "U2") (pin "4") (pinfunction "4_4") (pintype "passive+no_connect"))
    )
    (net (code "86") (name "unconnected-(U2-Pad5)") (class "Default")
      (node (ref "U2") (pin "5") (pinfunction "5_5") (pintype "passive+no_connect"))
    )
    (net (code "87") (name "unconnected-(U2-Pad6)") (class "Default")
      (node (ref "U2") (pin "6") (pinfunction "6_6") (pintype "passive+no_connect"))
    )
    (net (code "88") (name "unconnected-(U2-Pad7)") (class "Default")
      (node (ref "U2") (pin "7") (pinfunction "7_7") (pintype "passive+no_connect"))
    )
    (net (code "89") (name "unconnected-(U2-Pad16)") (class "Default")
      (node (ref "U2") (pin "16") (pinfunction "16_16") (pintype "passive+no_connect"))
    )
    (net (code "90") (name "unconnected-(U2-Pad17)") (class "Default")
      (node (ref "U2") (pin "17") (pinfunction "17_17") (pintype "passive+no_connect"))
    )
    (net (code "91") (name "unconnected-(U2-Pad18)") (class "Default")
      (node (ref "U2") (pin "18") (pinfunction "18_18") (pintype "passive+no_connect"))
    )
    (net (code "92") (name "unconnected-(U2-Pad19)") (class "Default")
      (node (ref "U2") (pin "19") (pinfunction "19_19") (pintype "passive+no_connect"))
    )
    (net (code "93") (name "unconnected-(U2-Pad20)") (class "Default")
      (node (ref "U2") (pin "20") (pinfunction "20_20") (pintype "passive+no_connect"))
    )
    (net (code "94") (name "unconnected-(U2-Pad21)") (class "Default")
      (node (ref "U2") (pin "21") (pinfunction "21_21") (pintype "passive+no_connect"))
    )
    (net (code "95") (name "unconnected-(U2-Pad22)") (class "Default")
      (node (ref "U2") (pin "22") (pinfunction "22_22") (pintype "passive+no_connect"))
    )
    (net (code "96") (name "unconnected-(U4-IMT-Pad7)") (class "Default")
      (node (ref "U4") (pin "7") (pinfunction "IMT_7") (pintype "passive+no_connect"))
    )
    (net (code "97") (name "unconnected-(U4-STAT-Pad4)") (class "Default")
      (node (ref "U4") (pin "4") (pinfunction "STAT_4") (pintype "passive+no_connect"))
    )
    (net (code "98") (name "unconnected-(microUSB-ID-Pad4)") (class "Default")
      (node (ref "microUSB") (pin "4") (pinfunction "ID_4") (pintype "passive+no_connect"))
    )
  )
)
